# MCU063A_EtherCAT.net
KiCad netlist of a schematic drawn in Altium Designer
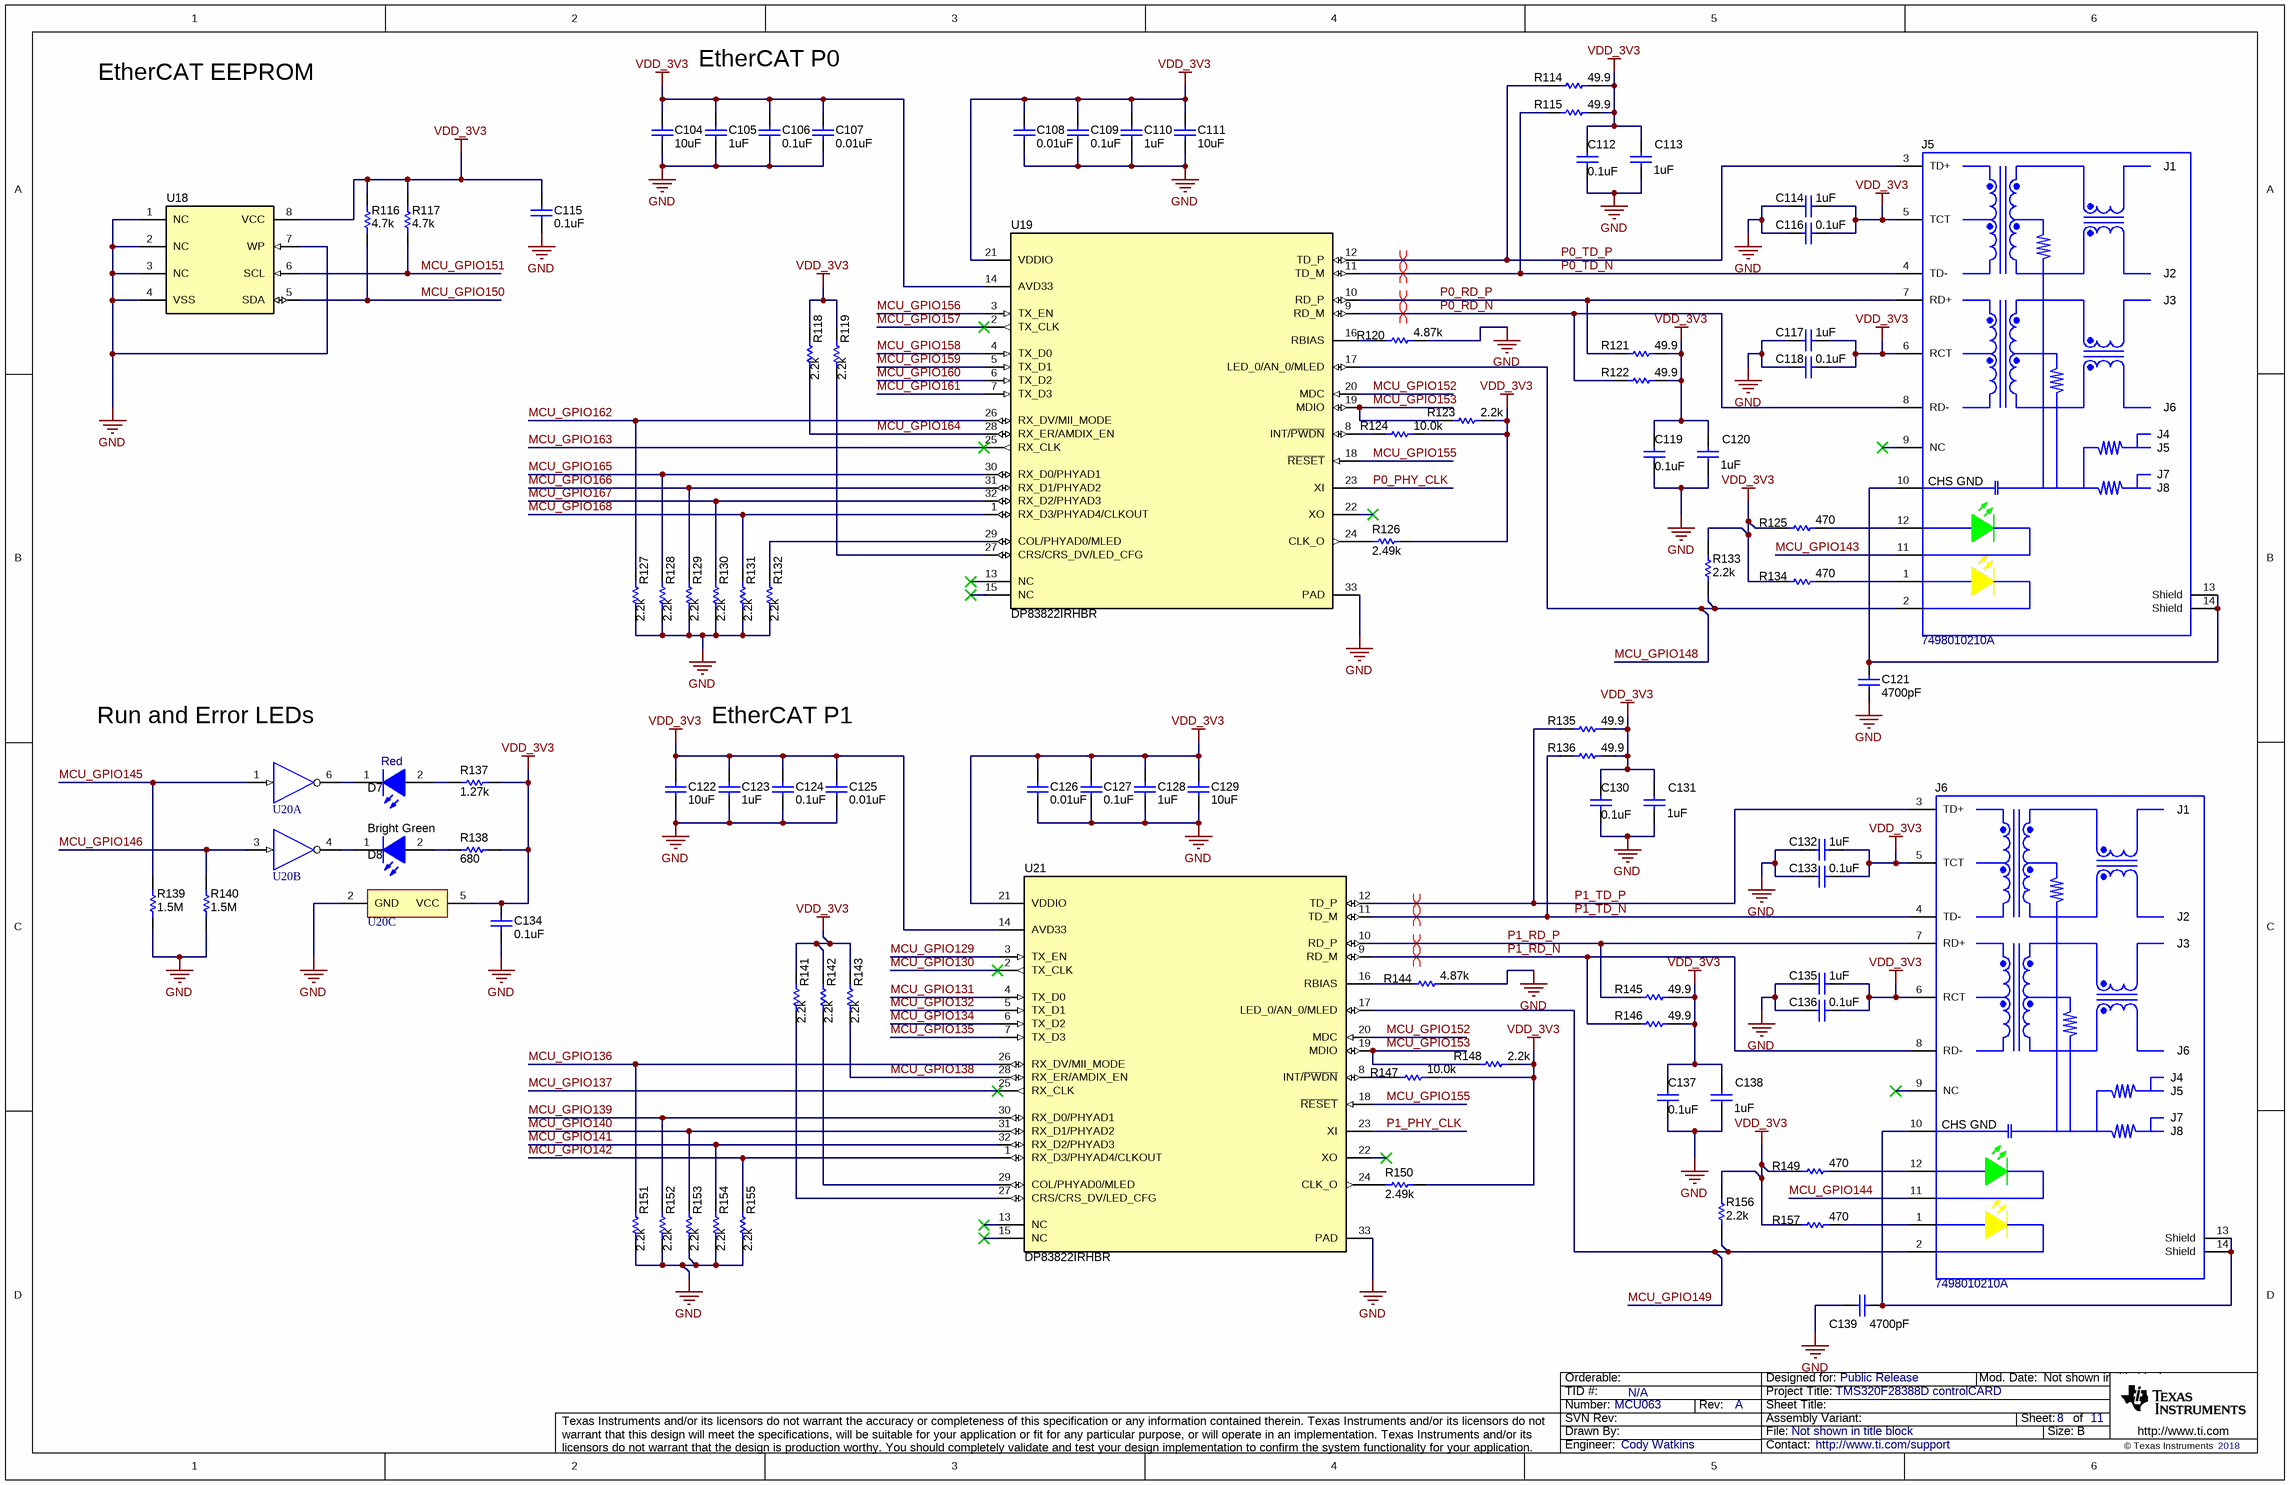
[diagram p0: MCU063A_EtherCAT.SchDoc]

(export (version "E")
  (design (tool "Eeschema 10.0.6"))
  (components
    (comp (ref "C104")
      (value "CL05A106MQ5NUNC")
      (footprint "0402")
      (description "CAP, CERM, 10 uF, 6.3 V, +/- 20%, X5R, 0402")
      (fields
        (field (name "MANUFACTURER") "Samsung Electro-Mechanics")
        (field (name "VALUEDISPLAYED") "10uF")
      )
      (libsource (lib "Altium Vault - TI") (part "Capacitor"))
    )
    (comp (ref "C105")
      (value "EMK105BJ105KVHF")
      (footprint "0402")
      (description "CAP, CERM, 1 uF, 16 V, +/- 10%, X5R, 0402")
      (fields (field (name "MANUFACTURER") "Taiyo Yuden") (field (name "VALUEDISPLAYED") "1uF"))
      (libsource (lib "Altium Vault - TI") (part "Capacitor"))
    )
    (comp (ref "C106")
      (value "LMK105BJ104KV-F")
      (footprint "0402")
      (description "CAP, CERM, 0.1 uF, 10 V,+/- 10%, X5R, 0402")
      (fields (field (name "MANUFACTURER") "Taiyo Yuden") (field (name "VALUEDISPLAYED") "0.1uF"))
      (libsource (lib "Altium Vault - TI") (part "Capacitor"))
    )
    (comp (ref "C107")
      (value "885012205031")
      (footprint "0402")
      (description "CAP, CERM, 0.01 uF, 16 V, +/- 10%, X7R, 0402")
      (fields (field (name "MANUFACTURER") "Wurth Elektronik") (field (name "VALUEDISPLAYED") "0.01uF"))
      (libsource (lib "Altium Vault - TI") (part "Capacitor"))
    )
    (comp (ref "C108")
      (value "885012205031")
      (footprint "0402")
      (description "CAP, CERM, 0.01 uF, 16 V, +/- 10%, X7R, 0402")
      (fields (field (name "MANUFACTURER") "Wurth Elektronik") (field (name "VALUEDISPLAYED") "0.01uF"))
      (libsource (lib "Altium Vault - TI") (part "Capacitor"))
    )
    (comp (ref "C109")
      (value "LMK105BJ104KV-F")
      (footprint "0402")
      (description "CAP, CERM, 0.1 uF, 10 V,+/- 10%, X5R, 0402")
      (fields (field (name "MANUFACTURER") "Taiyo Yuden") (field (name "VALUEDISPLAYED") "0.1uF"))
      (libsource (lib "Altium Vault - TI") (part "Capacitor"))
    )
    (comp (ref "C110")
      (value "EMK105BJ105KVHF")
      (footprint "0402")
      (description "CAP, CERM, 1 uF, 16 V, +/- 10%, X5R, 0402")
      (fields (field (name "MANUFACTURER") "Taiyo Yuden") (field (name "VALUEDISPLAYED") "1uF"))
      (libsource (lib "Altium Vault - TI") (part "Capacitor"))
    )
    (comp (ref "C111")
      (value "CL05A106MQ5NUNC")
      (footprint "0402")
      (description "CAP, CERM, 10 uF, 6.3 V, +/- 20%, X5R, 0402")
      (fields
        (field (name "MANUFACTURER") "Samsung Electro-Mechanics")
        (field (name "VALUEDISPLAYED") "10uF")
      )
      (libsource (lib "Altium Vault - TI") (part "Capacitor"))
    )
    (comp (ref "C112")
      (value "LMK105BJ104KV-F")
      (footprint "0402")
      (description "CAP, CERM, 0.1 uF, 10 V,+/- 10%, X5R, 0402")
      (fields (field (name "MANUFACTURER") "Taiyo Yuden") (field (name "VALUEDISPLAYED") "0.1uF"))
      (libsource (lib "Altium Vault - TI") (part "Capacitor"))
    )
    (comp (ref "C113")
      (value "EMK105BJ105KVHF")
      (footprint "0402")
      (description "CAP, CERM, 1 uF, 16 V, +/- 10%, X5R, 0402")
      (fields (field (name "MANUFACTURER") "Taiyo Yuden") (field (name "VALUEDISPLAYED") "1uF"))
      (libsource (lib "Altium Vault - TI") (part "Capacitor"))
    )
    (comp (ref "C114")
      (value "EMK105BJ105KVHF")
      (footprint "0402")
      (description "CAP, CERM, 1 uF, 16 V, +/- 10%, X5R, 0402")
      (fields (field (name "MANUFACTURER") "Taiyo Yuden") (field (name "VALUEDISPLAYED") "1uF"))
      (libsource (lib "Altium Vault - TI") (part "Capacitor"))
    )
    (comp (ref "C115")
      (value "CL05B104KP5NNNC")
      (footprint "0402")
      (description "CAP, CERM, 0.1 uF, 10 V, +/- 10%, X7R, 0402")
      (fields
        (field (name "VALUEDISPLAYED") "0.1uF")
        (field (name "MANUFACTURER") "Samsung Electro-Mechanics")
      )
      (libsource (lib "Altium Vault - TI") (part "Capacitor"))
    )
    (comp (ref "C116")
      (value "LMK105BJ104KV-F")
      (footprint "0402")
      (description "CAP, CERM, 0.1 uF, 10 V,+/- 10%, X5R, 0402")
      (fields (field (name "MANUFACTURER") "Taiyo Yuden") (field (name "VALUEDISPLAYED") "0.1uF"))
      (libsource (lib "Altium Vault - TI") (part "Capacitor"))
    )
    (comp (ref "C117")
      (value "EMK105BJ105KVHF")
      (footprint "0402")
      (description "CAP, CERM, 1 uF, 16 V, +/- 10%, X5R, 0402")
      (fields (field (name "MANUFACTURER") "Taiyo Yuden") (field (name "VALUEDISPLAYED") "1uF"))
      (libsource (lib "Altium Vault - TI") (part "Capacitor"))
    )
    (comp (ref "C118")
      (value "LMK105BJ104KV-F")
      (footprint "0402")
      (description "CAP, CERM, 0.1 uF, 10 V,+/- 10%, X5R, 0402")
      (fields (field (name "MANUFACTURER") "Taiyo Yuden") (field (name "VALUEDISPLAYED") "0.1uF"))
      (libsource (lib "Altium Vault - TI") (part "Capacitor"))
    )
    (comp (ref "C119")
      (value "LMK105BJ104KV-F")
      (footprint "0402")
      (description "CAP, CERM, 0.1 uF, 10 V,+/- 10%, X5R, 0402")
      (fields (field (name "MANUFACTURER") "Taiyo Yuden") (field (name "VALUEDISPLAYED") "0.1uF"))
      (libsource (lib "Altium Vault - TI") (part "Capacitor"))
    )
    (comp (ref "C120")
      (value "EMK105BJ105KVHF")
      (footprint "0402")
      (description "CAP, CERM, 1 uF, 16 V, +/- 10%, X5R, 0402")
      (fields (field (name "MANUFACTURER") "Taiyo Yuden") (field (name "VALUEDISPLAYED") "1uF"))
      (libsource (lib "Altium Vault - TI") (part "Capacitor"))
    )
    (comp (ref "C121")
      (value "12061C472KAT2A")
      (footprint "1206")
      (description "CAP, CERM, 4700 pF, 100 V, +/- 10%, X7R, 1206")
      (fields (field (name "MANUFACTURER") "AVX") (field (name "VALUEDISPLAYED") "4700pF"))
      (libsource (lib "Altium Vault - TI") (part "Capacitor"))
    )
    (comp (ref "C122")
      (value "CL05A106MQ5NUNC")
      (footprint "0402")
      (description "CAP, CERM, 10 uF, 6.3 V, +/- 20%, X5R, 0402")
      (fields
        (field (name "MANUFACTURER") "Samsung Electro-Mechanics")
        (field (name "VALUEDISPLAYED") "10uF")
      )
      (libsource (lib "Altium Vault - TI") (part "Capacitor"))
    )
    (comp (ref "C123")
      (value "EMK105BJ105KVHF")
      (footprint "0402")
      (description "CAP, CERM, 1 uF, 16 V, +/- 10%, X5R, 0402")
      (fields (field (name "MANUFACTURER") "Taiyo Yuden") (field (name "VALUEDISPLAYED") "1uF"))
      (libsource (lib "Altium Vault - TI") (part "Capacitor"))
    )
    (comp (ref "C124")
      (value "LMK105BJ104KV-F")
      (footprint "0402")
      (description "CAP, CERM, 0.1 uF, 10 V,+/- 10%, X5R, 0402")
      (fields (field (name "MANUFACTURER") "Taiyo Yuden") (field (name "VALUEDISPLAYED") "0.1uF"))
      (libsource (lib "Altium Vault - TI") (part "Capacitor"))
    )
    (comp (ref "C125")
      (value "885012205031")
      (footprint "0402")
      (description "CAP, CERM, 0.01 uF, 16 V, +/- 10%, X7R, 0402")
      (fields (field (name "MANUFACTURER") "Wurth Elektronik") (field (name "VALUEDISPLAYED") "0.01uF"))
      (libsource (lib "Altium Vault - TI") (part "Capacitor"))
    )
    (comp (ref "C126")
      (value "885012205031")
      (footprint "0402")
      (description "CAP, CERM, 0.01 uF, 16 V, +/- 10%, X7R, 0402")
      (fields (field (name "MANUFACTURER") "Wurth Elektronik") (field (name "VALUEDISPLAYED") "0.01uF"))
      (libsource (lib "Altium Vault - TI") (part "Capacitor"))
    )
    (comp (ref "C127")
      (value "LMK105BJ104KV-F")
      (footprint "0402")
      (description "CAP, CERM, 0.1 uF, 10 V,+/- 10%, X5R, 0402")
      (fields (field (name "MANUFACTURER") "Taiyo Yuden") (field (name "VALUEDISPLAYED") "0.1uF"))
      (libsource (lib "Altium Vault - TI") (part "Capacitor"))
    )
    (comp (ref "C128")
      (value "EMK105BJ105KVHF")
      (footprint "0402")
      (description "CAP, CERM, 1 uF, 16 V, +/- 10%, X5R, 0402")
      (fields (field (name "MANUFACTURER") "Taiyo Yuden") (field (name "VALUEDISPLAYED") "1uF"))
      (libsource (lib "Altium Vault - TI") (part "Capacitor"))
    )
    (comp (ref "C129")
      (value "CL05A106MQ5NUNC")
      (footprint "0402")
      (description "CAP, CERM, 10 uF, 6.3 V, +/- 20%, X5R, 0402")
      (fields
        (field (name "MANUFACTURER") "Samsung Electro-Mechanics")
        (field (name "VALUEDISPLAYED") "10uF")
      )
      (libsource (lib "Altium Vault - TI") (part "Capacitor"))
    )
    (comp (ref "C130")
      (value "LMK105BJ104KV-F")
      (footprint "0402")
      (description "CAP, CERM, 0.1 uF, 10 V,+/- 10%, X5R, 0402")
      (fields (field (name "MANUFACTURER") "Taiyo Yuden") (field (name "VALUEDISPLAYED") "0.1uF"))
      (libsource (lib "Altium Vault - TI") (part "Capacitor"))
    )
    (comp (ref "C131")
      (value "EMK105BJ105KVHF")
      (footprint "0402")
      (description "CAP, CERM, 1 uF, 16 V, +/- 10%, X5R, 0402")
      (fields (field (name "MANUFACTURER") "Taiyo Yuden") (field (name "VALUEDISPLAYED") "1uF"))
      (libsource (lib "Altium Vault - TI") (part "Capacitor"))
    )
    (comp (ref "C132")
      (value "EMK105BJ105KVHF")
      (footprint "0402")
      (description "CAP, CERM, 1 uF, 16 V, +/- 10%, X5R, 0402")
      (fields (field (name "MANUFACTURER") "Taiyo Yuden") (field (name "VALUEDISPLAYED") "1uF"))
      (libsource (lib "Altium Vault - TI") (part "Capacitor"))
    )
    (comp (ref "C133")
      (value "LMK105BJ104KV-F")
      (footprint "0402")
      (description "CAP, CERM, 0.1 uF, 10 V,+/- 10%, X5R, 0402")
      (fields (field (name "MANUFACTURER") "Taiyo Yuden") (field (name "VALUEDISPLAYED") "0.1uF"))
      (libsource (lib "Altium Vault - TI") (part "Capacitor"))
    )
    (comp (ref "C134")
      (value "CL05B104KP5NNNC")
      (footprint "0402")
      (description "CAP, CERM, 0.1 uF, 10 V, +/- 10%, X7R, 0402")
      (fields
        (field (name "VALUEDISPLAYED") "0.1uF")
        (field (name "MANUFACTURER") "Samsung Electro-Mechanics")
      )
      (libsource (lib "Altium Vault - TI") (part "Capacitor"))
    )
    (comp (ref "C135")
      (value "EMK105BJ105KVHF")
      (footprint "0402")
      (description "CAP, CERM, 1 uF, 16 V, +/- 10%, X5R, 0402")
      (fields (field (name "MANUFACTURER") "Taiyo Yuden") (field (name "VALUEDISPLAYED") "1uF"))
      (libsource (lib "Altium Vault - TI") (part "Capacitor"))
    )
    (comp (ref "C136")
      (value "LMK105BJ104KV-F")
      (footprint "0402")
      (description "CAP, CERM, 0.1 uF, 10 V,+/- 10%, X5R, 0402")
      (fields (field (name "MANUFACTURER") "Taiyo Yuden") (field (name "VALUEDISPLAYED") "0.1uF"))
      (libsource (lib "Altium Vault - TI") (part "Capacitor"))
    )
    (comp (ref "C137")
      (value "LMK105BJ104KV-F")
      (footprint "0402")
      (description "CAP, CERM, 0.1 uF, 10 V,+/- 10%, X5R, 0402")
      (fields (field (name "MANUFACTURER") "Taiyo Yuden") (field (name "VALUEDISPLAYED") "0.1uF"))
      (libsource (lib "Altium Vault - TI") (part "Capacitor"))
    )
    (comp (ref "C138")
      (value "EMK105BJ105KVHF")
      (footprint "0402")
      (description "CAP, CERM, 1 uF, 16 V, +/- 10%, X5R, 0402")
      (fields (field (name "MANUFACTURER") "Taiyo Yuden") (field (name "VALUEDISPLAYED") "1uF"))
      (libsource (lib "Altium Vault - TI") (part "Capacitor"))
    )
    (comp (ref "C139")
      (value "12061C472KAT2A")
      (footprint "1206")
      (description "CAP, CERM, 4700 pF, 100 V, +/- 10%, X7R, 1206")
      (fields (field (name "MANUFACTURER") "AVX") (field (name "VALUEDISPLAYED") "4700pF"))
      (libsource (lib "Altium Vault - TI") (part "Capacitor"))
    )
    (comp (ref "D7")
      (value "Red")
      (footprint "WL-SMCW_RED_0805")
      (description "LED, Red, SMD")
      (fields (field (name "PARTNUMBER") "150080SS75000") (field (name "MANUFACTURER") "Wurth Elektronik"))
      (libsource (lib "Altium Vault - TI") (part "LED_A2_K1"))
    )
    (comp (ref "D8")
      (value "Bright Green")
      (footprint "WL-SMCW_Green_0805")
      (description "LED, Bright Green, SMD")
      (fields (field (name "PARTNUMBER") "150080VS75000") (field (name "MANUFACTURER") "Wurth Elektronik"))
      (libsource (lib "Altium Vault - TI") (part "LED_A2_K1"))
    )
    (comp (ref "J5")
      (value "7498010210A")
      (footprint "Wurth_7498010210A")
      (description "Connector, RJ45, 1x1, Gold, R/A, SMT")
      (fields (field (name "MANUFACTURER") "Wurth Elektronik"))
      (libsource (lib "Altium Vault - TI") (part "Wurth_7498010210A"))
    )
    (comp (ref "J6")
      (value "7498010210A")
      (footprint "Wurth_7498010210A")
      (description "Connector, RJ45, 1x1, Gold, R/A, SMT")
      (fields (field (name "MANUFACTURER") "Wurth Elektronik"))
      (libsource (lib "Altium Vault - TI") (part "Wurth_7498010210A"))
    )
    (comp (ref "R114")
      (value "RC0402FR-0749R9L")
      (footprint "0402")
      (description "RES, 49.9, 1%, 0.063 W, 0402")
      (fields (field (name "MANUFACTURER") "Yageo America") (field (name "VALUEDISPLAYED") "49.9"))
      (libsource (lib "Altium Vault - TI") (part "Resistor"))
    )
    (comp (ref "R115")
      (value "RC0402FR-0749R9L")
      (footprint "0402")
      (description "RES, 49.9, 1%, 0.063 W, 0402")
      (fields (field (name "MANUFACTURER") "Yageo America") (field (name "VALUEDISPLAYED") "49.9"))
      (libsource (lib "Altium Vault - TI") (part "Resistor"))
    )
    (comp (ref "R116")
      (value "CRCW04024K70JNED")
      (footprint "0402")
      (description "RES, 4.7 k, 5%, 0.063 W, AEC-Q200 Grade 0, 0402")
      (fields (field (name "MANUFACTURER") "Vishay-Dale") (field (name "VALUEDISPLAYED") "4.7k"))
      (libsource (lib "Altium Vault - TI") (part "Resistor"))
    )
    (comp (ref "R117")
      (value "CRCW04024K70JNED")
      (footprint "0402")
      (description "RES, 4.7 k, 5%, 0.063 W, AEC-Q200 Grade 0, 0402")
      (fields (field (name "MANUFACTURER") "Vishay-Dale") (field (name "VALUEDISPLAYED") "4.7k"))
      (libsource (lib "Altium Vault - TI") (part "Resistor"))
    )
    (comp (ref "R118")
      (value "CRCW02012K20JNED")
      (footprint "0201")
      (description "RES, 2.2 k, 5%, 0.05 W, 0201")
      (fields (field (name "MANUFACTURER") "Vishay-Dale") (field (name "VALUEDISPLAYED") "2.2k"))
      (libsource (lib "Altium Vault - TI") (part "Resistor"))
    )
    (comp (ref "R119")
      (value "CRCW02012K20JNED")
      (footprint "0201")
      (description "RES, 2.2 k, 5%, 0.05 W, 0201")
      (fields (field (name "MANUFACTURER") "Vishay-Dale") (field (name "VALUEDISPLAYED") "2.2k"))
      (libsource (lib "Altium Vault - TI") (part "Resistor"))
    )
    (comp (ref "R120")
      (value "CRCW04024K87FKED")
      (footprint "0402")
      (description "RES, 4.87 k, 1%, 0.063 W, AEC-Q200 Grade 0, 0402")
      (fields (field (name "MANUFACTURER") "Vishay-Dale") (field (name "VALUEDISPLAYED") "4.87k"))
      (libsource (lib "Altium Vault - TI") (part "Resistor"))
    )
    (comp (ref "R121")
      (value "RC0402FR-0749R9L")
      (footprint "0402")
      (description "RES, 49.9, 1%, 0.063 W, 0402")
      (fields (field (name "MANUFACTURER") "Yageo America") (field (name "VALUEDISPLAYED") "49.9"))
      (libsource (lib "Altium Vault - TI") (part "Resistor"))
    )
    (comp (ref "R122")
      (value "RC0402FR-0749R9L")
      (footprint "0402")
      (description "RES, 49.9, 1%, 0.063 W, 0402")
      (fields (field (name "MANUFACTURER") "Yageo America") (field (name "VALUEDISPLAYED") "49.9"))
      (libsource (lib "Altium Vault - TI") (part "Resistor"))
    )
    (comp (ref "R123")
      (value "CRCW04022K20JNED")
      (footprint "0402")
      (description "RES, 2.2 k, 5%, 0.063 W, AEC-Q200 Grade 0, 0402")
      (fields (field (name "MANUFACTURER") "Vishay-Dale") (field (name "VALUEDISPLAYED") "2.2k"))
      (libsource (lib "Altium Vault - TI") (part "Resistor"))
    )
    (comp (ref "R124")
      (value "RC0402FR-0710KL")
      (footprint "0402")
      (description "RES, 10.0 k, 1%, 0.063 W, 0402")
      (fields (field (name "MANUFACTURER") "Yageo America") (field (name "VALUEDISPLAYED") "10.0k"))
      (libsource (lib "Altium Vault - TI") (part "Resistor"))
    )
    (comp (ref "R125")
      (value "CRCW0603470RJNEA")
      (footprint "0603")
      (description "RES, 470, 5%, 0.1 W, AEC-Q200 Grade 0, 0603")
      (fields (field (name "MANUFACTURER") "Vishay-Dale") (field (name "VALUEDISPLAYED") "470"))
      (libsource (lib "Altium Vault - TI") (part "Resistor"))
    )
    (comp (ref "R126")
      (value "CRCW04022K49FKED")
      (footprint "0402")
      (description "RES, 2.49 k, 1%, 0.063 W, AEC-Q200 Grade 0, 0402")
      (fields (field (name "MANUFACTURER") "Vishay-Dale") (field (name "VALUEDISPLAYED") "2.49k"))
      (libsource (lib "Altium Vault - TI") (part "Resistor"))
    )
    (comp (ref "R127")
      (value "CRCW02012K20JNED")
      (footprint "0201")
      (description "RES, 2.2 k, 5%, 0.05 W, 0201")
      (fields (field (name "MANUFACTURER") "Vishay-Dale") (field (name "VALUEDISPLAYED") "2.2k"))
      (libsource (lib "Altium Vault - TI") (part "Resistor"))
    )
    (comp (ref "R128")
      (value "CRCW02012K20JNED")
      (footprint "0201")
      (description "RES, 2.2 k, 5%, 0.05 W, 0201")
      (fields (field (name "MANUFACTURER") "Vishay-Dale") (field (name "VALUEDISPLAYED") "2.2k"))
      (libsource (lib "Altium Vault - TI") (part "Resistor"))
    )
    (comp (ref "R129")
      (value "CRCW02012K20JNED")
      (footprint "0201")
      (description "RES, 2.2 k, 5%, 0.05 W, 0201")
      (fields (field (name "MANUFACTURER") "Vishay-Dale") (field (name "VALUEDISPLAYED") "2.2k"))
      (libsource (lib "Altium Vault - TI") (part "Resistor"))
    )
    (comp (ref "R130")
      (value "CRCW02012K20JNED")
      (footprint "0201")
      (description "RES, 2.2 k, 5%, 0.05 W, 0201")
      (fields (field (name "MANUFACTURER") "Vishay-Dale") (field (name "VALUEDISPLAYED") "2.2k"))
      (libsource (lib "Altium Vault - TI") (part "Resistor"))
    )
    (comp (ref "R131")
      (value "CRCW02012K20JNED")
      (footprint "0201")
      (description "RES, 2.2 k, 5%, 0.05 W, 0201")
      (fields (field (name "MANUFACTURER") "Vishay-Dale") (field (name "VALUEDISPLAYED") "2.2k"))
      (libsource (lib "Altium Vault - TI") (part "Resistor"))
    )
    (comp (ref "R132")
      (value "CRCW02012K20JNED")
      (footprint "0201")
      (description "RES, 2.2 k, 5%, 0.05 W, 0201")
      (fields (field (name "MANUFACTURER") "Vishay-Dale") (field (name "VALUEDISPLAYED") "2.2k"))
      (libsource (lib "Altium Vault - TI") (part "Resistor"))
    )
    (comp (ref "R133")
      (value "CRCW04022K20JNED")
      (footprint "0402")
      (description "RES, 2.2 k, 5%, 0.063 W, AEC-Q200 Grade 0, 0402")
      (fields (field (name "MANUFACTURER") "Vishay-Dale") (field (name "VALUEDISPLAYED") "2.2k"))
      (libsource (lib "Altium Vault - TI") (part "Resistor"))
    )
    (comp (ref "R134")
      (value "CRCW0603470RJNEA")
      (footprint "0603")
      (description "RES, 470, 5%, 0.1 W, AEC-Q200 Grade 0, 0603")
      (fields (field (name "MANUFACTURER") "Vishay-Dale") (field (name "VALUEDISPLAYED") "470"))
      (libsource (lib "Altium Vault - TI") (part "Resistor"))
    )
    (comp (ref "R135")
      (value "RC0402FR-0749R9L")
      (footprint "0402")
      (description "RES, 49.9, 1%, 0.063 W, 0402")
      (fields (field (name "MANUFACTURER") "Yageo America") (field (name "VALUEDISPLAYED") "49.9"))
      (libsource (lib "Altium Vault - TI") (part "Resistor"))
    )
    (comp (ref "R136")
      (value "RC0402FR-0749R9L")
      (footprint "0402")
      (description "RES, 49.9, 1%, 0.063 W, 0402")
      (fields (field (name "MANUFACTURER") "Yageo America") (field (name "VALUEDISPLAYED") "49.9"))
      (libsource (lib "Altium Vault - TI") (part "Resistor"))
    )
    (comp (ref "R137")
      (value "CRCW04021K27FKED")
      (footprint "0402")
      (description "RES, 1.27 k, 1%, 0.063 W, AEC-Q200 Grade 0, 0402")
      (fields (field (name "MANUFACTURER") "Vishay-Dale") (field (name "VALUEDISPLAYED") "1.27k"))
      (libsource (lib "Altium Vault - TI") (part "Resistor"))
    )
    (comp (ref "R138")
      (value "CRCW0402680RJNED")
      (footprint "0402")
      (description "RES, 680, 5%, 0.063 W, AEC-Q200 Grade 0, 0402")
      (fields (field (name "VALUEDISPLAYED") "680") (field (name "MANUFACTURER") "Vishay-Dale"))
      (libsource (lib "Altium Vault - TI") (part "Resistor"))
    )
    (comp (ref "R139")
      (value "CRCW04021M50JNED")
      (footprint "0402")
      (description "RES, 1.5 M, 5%, 0.063 W, AEC-Q200 Grade 0, 0402")
      (fields (field (name "MANUFACTURER") "Vishay-Dale") (field (name "VALUEDISPLAYED") "1.5M"))
      (libsource (lib "Altium Vault - TI") (part "Resistor"))
    )
    (comp (ref "R140")
      (value "CRCW04021M50JNED")
      (footprint "0402")
      (description "RES, 1.5 M, 5%, 0.063 W, AEC-Q200 Grade 0, 0402")
      (fields (field (name "MANUFACTURER") "Vishay-Dale") (field (name "VALUEDISPLAYED") "1.5M"))
      (libsource (lib "Altium Vault - TI") (part "Resistor"))
    )
    (comp (ref "R141")
      (value "CRCW02012K20JNED")
      (footprint "0201")
      (description "RES, 2.2 k, 5%, 0.05 W, 0201")
      (fields (field (name "MANUFACTURER") "Vishay-Dale") (field (name "VALUEDISPLAYED") "2.2k"))
      (libsource (lib "Altium Vault - TI") (part "Resistor"))
    )
    (comp (ref "R142")
      (value "CRCW02012K20JNED")
      (footprint "0201")
      (description "RES, 2.2 k, 5%, 0.05 W, 0201")
      (fields (field (name "MANUFACTURER") "Vishay-Dale") (field (name "VALUEDISPLAYED") "2.2k"))
      (libsource (lib "Altium Vault - TI") (part "Resistor"))
    )
    (comp (ref "R143")
      (value "CRCW02012K20JNED")
      (footprint "0201")
      (description "RES, 2.2 k, 5%, 0.05 W, 0201")
      (fields (field (name "MANUFACTURER") "Vishay-Dale") (field (name "VALUEDISPLAYED") "2.2k"))
      (libsource (lib "Altium Vault - TI") (part "Resistor"))
    )
    (comp (ref "R144")
      (value "CRCW04024K87FKED")
      (footprint "0402")
      (description "RES, 4.87 k, 1%, 0.063 W, AEC-Q200 Grade 0, 0402")
      (fields (field (name "MANUFACTURER") "Vishay-Dale") (field (name "VALUEDISPLAYED") "4.87k"))
      (libsource (lib "Altium Vault - TI") (part "Resistor"))
    )
    (comp (ref "R145")
      (value "RC0402FR-0749R9L")
      (footprint "0402")
      (description "RES, 49.9, 1%, 0.063 W, 0402")
      (fields (field (name "MANUFACTURER") "Yageo America") (field (name "VALUEDISPLAYED") "49.9"))
      (libsource (lib "Altium Vault - TI") (part "Resistor"))
    )
    (comp (ref "R146")
      (value "RC0402FR-0749R9L")
      (footprint "0402")
      (description "RES, 49.9, 1%, 0.063 W, 0402")
      (fields (field (name "MANUFACTURER") "Yageo America") (field (name "VALUEDISPLAYED") "49.9"))
      (libsource (lib "Altium Vault - TI") (part "Resistor"))
    )
    (comp (ref "R147")
      (value "RC0402FR-0710KL")
      (footprint "0402")
      (description "RES, 10.0 k, 1%, 0.063 W, 0402")
      (fields (field (name "MANUFACTURER") "Yageo America") (field (name "VALUEDISPLAYED") "10.0k"))
      (libsource (lib "Altium Vault - TI") (part "Resistor"))
    )
    (comp (ref "R148")
      (value "CRCW04022K20JNED")
      (footprint "0402")
      (description "RES, 2.2 k, 5%, 0.063 W, AEC-Q200 Grade 0, 0402")
      (fields (field (name "MANUFACTURER") "Vishay-Dale") (field (name "VALUEDISPLAYED") "2.2k"))
      (libsource (lib "Altium Vault - TI") (part "Resistor"))
    )
    (comp (ref "R149")
      (value "CRCW0603470RJNEA")
      (footprint "0603")
      (description "RES, 470, 5%, 0.1 W, AEC-Q200 Grade 0, 0603")
      (fields (field (name "MANUFACTURER") "Vishay-Dale") (field (name "VALUEDISPLAYED") "470"))
      (libsource (lib "Altium Vault - TI") (part "Resistor"))
    )
    (comp (ref "R150")
      (value "CRCW04022K49FKED")
      (footprint "0402")
      (description "RES, 2.49 k, 1%, 0.063 W, AEC-Q200 Grade 0, 0402")
      (fields (field (name "MANUFACTURER") "Vishay-Dale") (field (name "VALUEDISPLAYED") "2.49k"))
      (libsource (lib "Altium Vault - TI") (part "Resistor"))
    )
    (comp (ref "R151")
      (value "CRCW02012K20JNED")
      (footprint "0201")
      (description "RES, 2.2 k, 5%, 0.05 W, 0201")
      (fields (field (name "MANUFACTURER") "Vishay-Dale") (field (name "VALUEDISPLAYED") "2.2k"))
      (libsource (lib "Altium Vault - TI") (part "Resistor"))
    )
    (comp (ref "R152")
      (value "CRCW02012K20JNED")
      (footprint "0201")
      (description "RES, 2.2 k, 5%, 0.05 W, 0201")
      (fields (field (name "MANUFACTURER") "Vishay-Dale") (field (name "VALUEDISPLAYED") "2.2k"))
      (libsource (lib "Altium Vault - TI") (part "Resistor"))
    )
    (comp (ref "R153")
      (value "CRCW02012K20JNED")
      (footprint "0201")
      (description "RES, 2.2 k, 5%, 0.05 W, 0201")
      (fields (field (name "MANUFACTURER") "Vishay-Dale") (field (name "VALUEDISPLAYED") "2.2k"))
      (libsource (lib "Altium Vault - TI") (part "Resistor"))
    )
    (comp (ref "R154")
      (value "CRCW02012K20JNED")
      (footprint "0201")
      (description "RES, 2.2 k, 5%, 0.05 W, 0201")
      (fields (field (name "MANUFACTURER") "Vishay-Dale") (field (name "VALUEDISPLAYED") "2.2k"))
      (libsource (lib "Altium Vault - TI") (part "Resistor"))
    )
    (comp (ref "R155")
      (value "CRCW02012K20JNED")
      (footprint "0201")
      (description "RES, 2.2 k, 5%, 0.05 W, 0201")
      (fields (field (name "MANUFACTURER") "Vishay-Dale") (field (name "VALUEDISPLAYED") "2.2k"))
      (libsource (lib "Altium Vault - TI") (part "Resistor"))
    )
    (comp (ref "R156")
      (value "CRCW04022K20JNED")
      (footprint "0402")
      (description "RES, 2.2 k, 5%, 0.063 W, AEC-Q200 Grade 0, 0402")
      (fields (field (name "MANUFACTURER") "Vishay-Dale") (field (name "VALUEDISPLAYED") "2.2k"))
      (libsource (lib "Altium Vault - TI") (part "Resistor"))
    )
    (comp (ref "R157")
      (value "CRCW0603470RJNEA")
      (footprint "0603")
      (description "RES, 470, 5%, 0.1 W, AEC-Q200 Grade 0, 0603")
      (fields (field (name "MANUFACTURER") "Vishay-Dale") (field (name "VALUEDISPLAYED") "470"))
      (libsource (lib "Altium Vault - TI") (part "Resistor"))
    )
    (comp (ref "U18")
      (value "CAT24C16WI-GT3")
      (footprint "SOIC-8")
      (description "16 Kb I2C EEPROM Serial, SOIC-8")
      (fields (field (name "MANUFACTURER") "ON Semiconductor"))
      (libsource (lib "Altium Vault - TI") (part "EEPROM_8P_1-3NC"))
    )
    (comp (ref "U19")
      (value "DP83822IRHBR")
      (footprint "RHB0032B")
      (description "Robust, Low Power 10/100 Ethernet Physical Layer Transceiver, RHB0032B (VQFN-32)")
      (fields
        (field (name "ALTERNATE PARTNUMBER") "DP83822IRHBT")
        (field (name "PARTNUMBER") "DP83822IRHBR")
        (field (name "MANUFACTURER") "Texas Instruments")
      )
      (libsource (lib "Altium Vault - TI") (part "DP83822"))
    )
    (comp (ref "U20")
      (value "SN74LVC2G06DBVR")
      (footprint "DBV0006A_N")
      (description "Dual Inverter Buffer/Driver with Open-Drain Output, DBV0006A, LARGE T&R")
      (fields
        (field (name "MANUFACTURER") "Texas Instruments")
        (field (name "GENERIC PART NUMBER") "SN74LVC2G06")
      )
      (libsource (lib "Altium Vault - TI") (part "TI-SN74XXX2G06-XX-6"))
    )
    (comp (ref "U21")
      (value "DP83822IRHBR")
      (footprint "RHB0032B")
      (description "Robust, Low Power 10/100 Ethernet Physical Layer Transceiver, RHB0032B (VQFN-32)")
      (fields
        (field (name "ALTERNATE PARTNUMBER") "DP83822IRHBT")
        (field (name "PARTNUMBER") "DP83822IRHBR")
        (field (name "MANUFACTURER") "Texas Instruments")
      )
      (libsource (lib "Altium Vault - TI") (part "DP83822"))
    )
  )
  (nets
    (net (code "1") (name "/MCU_GPIO129") (class "Default")
      (node (ref "U21") (pin "3") (pinfunction "TX_EN_3") (pintype "input"))
    )
    (net (code "2") (name "/MCU_GPIO130") (class "Default")
      (node (ref "U21") (pin "2") (pinfunction "TX_CLK_2") (pintype "output+no_connect"))
    )
    (net (code "3") (name "/MCU_GPIO131") (class "Default")
      (node (ref "U21") (pin "4") (pinfunction "TX_D0_4") (pintype "input"))
    )
    (net (code "4") (name "/MCU_GPIO132") (class "Default")
      (node (ref "U21") (pin "5") (pinfunction "TX_D1_5") (pintype "input"))
    )
    (net (code "5") (name "/MCU_GPIO134") (class "Default")
      (node (ref "U21") (pin "6") (pinfunction "TX_D2_6") (pintype "input"))
    )
    (net (code "6") (name "/MCU_GPIO135") (class "Default")
      (node (ref "U21") (pin "7") (pinfunction "TX_D3_7") (pintype "input"))
    )
    (net (code "7") (name "/MCU_GPIO136") (class "Default")
      (node (ref "R151") (pin "2") (pinfunction "2_2") (pintype "passive"))
      (node (ref "U21") (pin "26") (pinfunction "RX_DV/MII_MODE_26") (pintype "bidirectional"))
    )
    (net (code "8") (name "/MCU_GPIO137") (class "Default")
      (node (ref "U21") (pin "25") (pinfunction "RX_CLK_25") (pintype "output+no_connect"))
    )
    (net (code "9") (name "/MCU_GPIO138") (class "Default")
      (node (ref "R143") (pin "1") (pinfunction "1_1") (pintype "passive"))
      (node (ref "U21") (pin "28") (pinfunction "RX_ER/AMDIX_EN_28") (pintype "bidirectional"))
    )
    (net (code "10") (name "/MCU_GPIO139") (class "Default")
      (node (ref "R152") (pin "2") (pinfunction "2_2") (pintype "passive"))
      (node (ref "U21") (pin "30") (pinfunction "RX_D0/PHYAD1_30") (pintype "bidirectional"))
    )
    (net (code "11") (name "/MCU_GPIO140") (class "Default")
      (node (ref "R153") (pin "2") (pinfunction "2_2") (pintype "passive"))
      (node (ref "U21") (pin "31") (pinfunction "RX_D1/PHYAD2_31") (pintype "bidirectional"))
    )
    (net (code "12") (name "/MCU_GPIO141") (class "Default")
      (node (ref "R154") (pin "2") (pinfunction "2_2") (pintype "passive"))
      (node (ref "U21") (pin "32") (pinfunction "RX_D2/PHYAD3_32") (pintype "bidirectional"))
    )
    (net (code "13") (name "/MCU_GPIO142") (class "Default")
      (node (ref "R155") (pin "2") (pinfunction "2_2") (pintype "passive"))
      (node (ref "U21") (pin "1") (pinfunction "RX_D3/PHYAD4/CLKOUT_1") (pintype "bidirectional"))
    )
    (net (code "14") (name "/MCU_GPIO143") (class "Default")
      (node (ref "J5") (pin "11") (pinfunction "LEFT_LED_CATHODE_11") (pintype "passive"))
    )
    (net (code "15") (name "/MCU_GPIO144") (class "Default")
      (node (ref "J6") (pin "11") (pinfunction "LEFT_LED_CATHODE_11") (pintype "passive"))
    )
    (net (code "16") (name "/MCU_GPIO145") (class "Default")
      (node (ref "R139") (pin "1") (pinfunction "1_1") (pintype "passive"))
      (node (ref "U20") (pin "1") (pinfunction "1A_1") (pintype "input"))
    )
    (net (code "17") (name "/MCU_GPIO146") (class "Default")
      (node (ref "R140") (pin "1") (pinfunction "1_1") (pintype "passive"))
      (node (ref "U20") (pin "3") (pinfunction "2A_3") (pintype "input"))
    )
    (net (code "18") (name "/MCU_GPIO148") (class "Default")
      (node (ref "J5") (pin "2") (pinfunction "RIGHT_LED_CATHODE_2") (pintype "passive"))
      (node (ref "R133") (pin "1") (pinfunction "1_1") (pintype "passive"))
      (node (ref "U19") (pin "17") (pinfunction "LED_0/AN_0/MLED_17") (pintype "bidirectional"))
    )
    (net (code "19") (name "/MCU_GPIO149") (class "Default")
      (node (ref "J6") (pin "2") (pinfunction "RIGHT_LED_CATHODE_2") (pintype "passive"))
      (node (ref "R156") (pin "1") (pinfunction "1_1") (pintype "passive"))
      (node (ref "U21") (pin "17") (pinfunction "LED_0/AN_0/MLED_17") (pintype "bidirectional"))
    )
    (net (code "20") (name "/MCU_GPIO150") (class "Default")
      (node (ref "R116") (pin "1") (pinfunction "1_1") (pintype "passive"))
      (node (ref "U18") (pin "5") (pinfunction "SDA_5") (pintype "bidirectional"))
    )
    (net (code "21") (name "/MCU_GPIO151") (class "Default")
      (node (ref "R117") (pin "1") (pinfunction "1_1") (pintype "passive"))
      (node (ref "U18") (pin "6") (pinfunction "SCL_6") (pintype "input"))
    )
    (net (code "22") (name "/MCU_GPIO152") (class "Default")
      (node (ref "U19") (pin "20") (pinfunction "MDC_20") (pintype "input"))
      (node (ref "U21") (pin "20") (pinfunction "MDC_20") (pintype "input"))
    )
    (net (code "23") (name "/MCU_GPIO153") (class "Default")
      (node (ref "R123") (pin "2") (pinfunction "2_2") (pintype "passive"))
      (node (ref "R148") (pin "2") (pinfunction "2_2") (pintype "passive"))
      (node (ref "U19") (pin "19") (pinfunction "MDIO_19") (pintype "bidirectional"))
      (node (ref "U21") (pin "19") (pinfunction "MDIO_19") (pintype "bidirectional"))
    )
    (net (code "24") (name "/MCU_GPIO155") (class "Default")
      (node (ref "U19") (pin "18") (pinfunction "RESET_18") (pintype "input"))
      (node (ref "U21") (pin "18") (pinfunction "RESET_18") (pintype "input"))
    )
    (net (code "25") (name "/MCU_GPIO156") (class "Default")
      (node (ref "U19") (pin "3") (pinfunction "TX_EN_3") (pintype "input"))
    )
    (net (code "26") (name "/MCU_GPIO157") (class "Default")
      (node (ref "U19") (pin "2") (pinfunction "TX_CLK_2") (pintype "output+no_connect"))
    )
    (net (code "27") (name "/MCU_GPIO158") (class "Default")
      (node (ref "U19") (pin "4") (pinfunction "TX_D0_4") (pintype "input"))
    )
    (net (code "28") (name "/MCU_GPIO159") (class "Default")
      (node (ref "U19") (pin "5") (pinfunction "TX_D1_5") (pintype "input"))
    )
    (net (code "29") (name "/MCU_GPIO160") (class "Default")
      (node (ref "U19") (pin "6") (pinfunction "TX_D2_6") (pintype "input"))
    )
    (net (code "30") (name "/MCU_GPIO161") (class "Default")
      (node (ref "U19") (pin "7") (pinfunction "TX_D3_7") (pintype "input"))
    )
    (net (code "31") (name "/MCU_GPIO162") (class "Default")
      (node (ref "R127") (pin "2") (pinfunction "2_2") (pintype "passive"))
      (node (ref "U19") (pin "26") (pinfunction "RX_DV/MII_MODE_26") (pintype "bidirectional"))
    )
    (net (code "32") (name "/MCU_GPIO163") (class "Default")
      (node (ref "U19") (pin "25") (pinfunction "RX_CLK_25") (pintype "output+no_connect"))
    )
    (net (code "33") (name "/MCU_GPIO164") (class "Default")
      (node (ref "R118") (pin "1") (pinfunction "1_1") (pintype "passive"))
      (node (ref "U19") (pin "28") (pinfunction "RX_ER/AMDIX_EN_28") (pintype "bidirectional"))
    )
    (net (code "34") (name "/MCU_GPIO165") (class "Default")
      (node (ref "R128") (pin "2") (pinfunction "2_2") (pintype "passive"))
      (node (ref "U19") (pin "30") (pinfunction "RX_D0/PHYAD1_30") (pintype "bidirectional"))
    )
    (net (code "35") (name "/MCU_GPIO166") (class "Default")
      (node (ref "R129") (pin "2") (pinfunction "2_2") (pintype "passive"))
      (node (ref "U19") (pin "31") (pinfunction "RX_D1/PHYAD2_31") (pintype "bidirectional"))
    )
    (net (code "36") (name "/MCU_GPIO167") (class "Default")
      (node (ref "R130") (pin "2") (pinfunction "2_2") (pintype "passive"))
      (node (ref "U19") (pin "32") (pinfunction "RX_D2/PHYAD3_32") (pintype "bidirectional"))
    )
    (net (code "37") (name "/MCU_GPIO168") (class "Default")
      (node (ref "R131") (pin "2") (pinfunction "2_2") (pintype "passive"))
      (node (ref "U19") (pin "1") (pinfunction "RX_D3/PHYAD4/CLKOUT_1") (pintype "bidirectional"))
    )
    (net (code "38") (name "/P0_PHY_CLK") (class "Default")
      (node (ref "U19") (pin "23") (pinfunction "XI_23") (pintype "passive"))
    )
    (net (code "39") (name "/P0_RD_N") (class "Default")
      (node (ref "J5") (pin "8") (pinfunction "RD-_8") (pintype "passive"))
      (node (ref "R122") (pin "1") (pinfunction "1_1") (pintype "passive"))
      (node (ref "U19") (pin "9") (pinfunction "RD_M_9") (pintype "bidirectional"))
    )
    (net (code "40") (name "/P0_RD_P") (class "Default")
      (node (ref "J5") (pin "7") (pinfunction "RD+_7") (pintype "passive"))
      (node (ref "R121") (pin "1") (pinfunction "1_1") (pintype "passive"))
      (node (ref "U19") (pin "10") (pinfunction "RD_P_10") (pintype "bidirectional"))
    )
    (net (code "41") (name "/P0_TD_N") (class "Default")
      (node (ref "J5") (pin "4") (pinfunction "TD-_4") (pintype "passive"))
      (node (ref "R115") (pin "1") (pinfunction "1_1") (pintype "passive"))
      (node (ref "U19") (pin "11") (pinfunction "TD_M_11") (pintype "bidirectional"))
    )
    (net (code "42") (name "/P0_TD_P") (class "Default")
      (node (ref "J5") (pin "3") (pinfunction "TD+_3") (pintype "passive"))
      (node (ref "R114") (pin "1") (pinfunction "1_1") (pintype "passive"))
      (node (ref "U19") (pin "12") (pinfunction "TD_P_12") (pintype "bidirectional"))
    )
    (net (code "43") (name "/P1_PHY_CLK") (class "Default")
      (node (ref "U21") (pin "23") (pinfunction "XI_23") (pintype "passive"))
    )
    (net (code "44") (name "/P1_RD_N") (class "Default")
      (node (ref "J6") (pin "8") (pinfunction "RD-_8") (pintype "passive"))
      (node (ref "R146") (pin "1") (pinfunction "1_1") (pintype "passive"))
      (node (ref "U21") (pin "9") (pinfunction "RD_M_9") (pintype "bidirectional"))
    )
    (net (code "45") (name "/P1_RD_P") (class "Default")
      (node (ref "J6") (pin "7") (pinfunction "RD+_7") (pintype "passive"))
      (node (ref "R145") (pin "1") (pinfunction "1_1") (pintype "passive"))
      (node (ref "U21") (pin "10") (pinfunction "RD_P_10") (pintype "bidirectional"))
    )
    (net (code "46") (name "/P1_TD_N") (class "Default")
      (node (ref "J6") (pin "4") (pinfunction "TD-_4") (pintype "passive"))
      (node (ref "R136") (pin "1") (pinfunction "1_1") (pintype "passive"))
      (node (ref "U21") (pin "11") (pinfunction "TD_M_11") (pintype "bidirectional"))
    )
    (net (code "47") (name "/P1_TD_P") (class "Default")
      (node (ref "J6") (pin "3") (pinfunction "TD+_3") (pintype "passive"))
      (node (ref "R135") (pin "1") (pinfunction "1_1") (pintype "passive"))
      (node (ref "U21") (pin "12") (pinfunction "TD_P_12") (pintype "bidirectional"))
    )
    (net (code "48") (name "GND") (class "Default")
      (node (ref "C104") (pin "2") (pinfunction "2_2") (pintype "passive"))
      (node (ref "C105") (pin "2") (pinfunction "2_2") (pintype "passive"))
      (node (ref "C106") (pin "2") (pinfunction "2_2") (pintype "passive"))
      (node (ref "C107") (pin "2") (pinfunction "2_2") (pintype "passive"))
      (node (ref "C108") (pin "2") (pinfunction "2_2") (pintype "passive"))
      (node (ref "C109") (pin "2") (pinfunction "2_2") (pintype "passive"))
      (node (ref "C110") (pin "2") (pinfunction "2_2") (pintype "passive"))
      (node (ref "C111") (pin "2") (pinfunction "2_2") (pintype "passive"))
      (node (ref "C112") (pin "2") (pinfunction "2_2") (pintype "passive"))
      (node (ref "C113") (pin "2") (pinfunction "2_2") (pintype "passive"))
      (node (ref "C114") (pin "1") (pinfunction "1_1") (pintype "passive"))
      (node (ref "C115") (pin "2") (pinfunction "2_2") (pintype "passive"))
      (node (ref "C116") (pin "1") (pinfunction "1_1") (pintype "passive"))
      (node (ref "C117") (pin "1") (pinfunction "1_1") (pintype "passive"))
      (node (ref "C118") (pin "1") (pinfunction "1_1") (pintype "passive"))
      (node (ref "C119") (pin "2") (pinfunction "2_2") (pintype "passive"))
      (node (ref "C120") (pin "2") (pinfunction "2_2") (pintype "passive"))
      (node (ref "C121") (pin "1") (pinfunction "1_1") (pintype "passive"))
      (node (ref "C122") (pin "2") (pinfunction "2_2") (pintype "passive"))
      (node (ref "C123") (pin "2") (pinfunction "2_2") (pintype "passive"))
      (node (ref "C124") (pin "2") (pinfunction "2_2") (pintype "passive"))
      (node (ref "C125") (pin "2") (pinfunction "2_2") (pintype "passive"))
      (node (ref "C126") (pin "2") (pinfunction "2_2") (pintype "passive"))
      (node (ref "C127") (pin "2") (pinfunction "2_2") (pintype "passive"))
      (node (ref "C128") (pin "2") (pinfunction "2_2") (pintype "passive"))
      (node (ref "C129") (pin "2") (pinfunction "2_2") (pintype "passive"))
      (node (ref "C130") (pin "2") (pinfunction "2_2") (pintype "passive"))
      (node (ref "C131") (pin "2") (pinfunction "2_2") (pintype "passive"))
      (node (ref "C132") (pin "1") (pinfunction "1_1") (pintype "passive"))
      (node (ref "C133") (pin "1") (pinfunction "1_1") (pintype "passive"))
      (node (ref "C134") (pin "2") (pinfunction "2_2") (pintype "passive"))
      (node (ref "C135") (pin "1") (pinfunction "1_1") (pintype "passive"))
      (node (ref "C136") (pin "1") (pinfunction "1_1") (pintype "passive"))
      (node (ref "C137") (pin "2") (pinfunction "2_2") (pintype "passive"))
      (node (ref "C138") (pin "2") (pinfunction "2_2") (pintype "passive"))
      (node (ref "C139") (pin "1") (pinfunction "1_1") (pintype "passive"))
      (node (ref "R120") (pin "2") (pinfunction "2_2") (pintype "passive"))
      (node (ref "R127") (pin "1") (pinfunction "1_1") (pintype "passive"))
      (node (ref "R128") (pin "1") (pinfunction "1_1") (pintype "passive"))
      (node (ref "R129") (pin "1") (pinfunction "1_1") (pintype "passive"))
      (node (ref "R130") (pin "1") (pinfunction "1_1") (pintype "passive"))
      (node (ref "R131") (pin "1") (pinfunction "1_1") (pintype "passive"))
      (node (ref "R132") (pin "1") (pinfunction "1_1") (pintype "passive"))
      (node (ref "R139") (pin "2") (pinfunction "2_2") (pintype "passive"))
      (node (ref "R140") (pin "2") (pinfunction "2_2") (pintype "passive"))
      (node (ref "R144") (pin "2") (pinfunction "2_2") (pintype "passive"))
      (node (ref "R151") (pin "1") (pinfunction "1_1") (pintype "passive"))
      (node (ref "R152") (pin "1") (pinfunction "1_1") (pintype "passive"))
      (node (ref "R153") (pin "1") (pinfunction "1_1") (pintype "passive"))
      (node (ref "R154") (pin "1") (pinfunction "1_1") (pintype "passive"))
      (node (ref "R155") (pin "1") (pinfunction "1_1") (pintype "passive"))
      (node (ref "U18") (pin "1") (pinfunction "NC_1") (pintype "passive"))
      (node (ref "U18") (pin "2") (pinfunction "NC_2") (pintype "passive"))
      (node (ref "U18") (pin "3") (pinfunction "NC_3") (pintype "passive"))
      (node (ref "U18") (pin "4") (pinfunction "VSS_4") (pintype "power_in"))
      (node (ref "U18") (pin "7") (pinfunction "WP_7") (pintype "input"))
      (node (ref "U19") (pin "33") (pinfunction "PAD_33") (pintype "power_in"))
      (node (ref "U20") (pin "2") (pinfunction "GND_2") (pintype "power_in"))
      (node (ref "U21") (pin "33") (pinfunction "PAD_33") (pintype "power_in"))
    )
    (net (code "49") (name "Net-(D7-A)") (class "Default")
      (node (ref "D7") (pin "2") (pinfunction "A_2") (pintype "passive"))
      (node (ref "R137") (pin "1") (pinfunction "1_1") (pintype "passive"))
    )
    (net (code "50") (name "Net-(D7-K)") (class "Default")
      (node (ref "D7") (pin "1") (pinfunction "K_1") (pintype "passive"))
      (node (ref "U20") (pin "6") (pinfunction "1Y_6") (pintype "open_collector"))
    )
    (net (code "51") (name "Net-(D8-A)") (class "Default")
      (node (ref "D8") (pin "2") (pinfunction "A_2") (pintype "passive"))
      (node (ref "R138") (pin "2") (pinfunction "2_2") (pintype "passive"))
    )
    (net (code "52") (name "Net-(D8-K)") (class "Default")
      (node (ref "D8") (pin "1") (pinfunction "K_1") (pintype "passive"))
      (node (ref "U20") (pin "4") (pinfunction "2Y_4") (pintype "open_collector"))
    )
    (net (code "53") (name "Net-(J5-CHS_GND)") (class "Default")
      (node (ref "C121") (pin "2") (pinfunction "2_2") (pintype "passive"))
      (node (ref "J5") (pin "10") (pinfunction "CHS_GND_10") (pintype "power_in"))
      (node (ref "J5") (pin "13") (pinfunction "Shield_13") (pintype "passive"))
      (node (ref "J5") (pin "14") (pinfunction "Shield_14") (pintype "passive"))
    )
    (net (code "54") (name "Net-(J5-LEFT_LED_ANODE)") (class "Default")
      (node (ref "J5") (pin "12") (pinfunction "LEFT_LED_ANODE_12") (pintype "passive"))
      (node (ref "R125") (pin "2") (pinfunction "2_2") (pintype "passive"))
    )
    (net (code "55") (name "Net-(J5-RIGHT_LED_ANODE)") (class "Default")
      (node (ref "J5") (pin "1") (pinfunction "RIGHT_LED_ANODE_1") (pintype "passive"))
      (node (ref "R134") (pin "2") (pinfunction "2_2") (pintype "passive"))
    )
    (net (code "56") (name "Net-(J6-CHS_GND)") (class "Default")
      (node (ref "C139") (pin "2") (pinfunction "2_2") (pintype "passive"))
      (node (ref "J6") (pin "10") (pinfunction "CHS_GND_10") (pintype "power_in"))
      (node (ref "J6") (pin "13") (pinfunction "Shield_13") (pintype "passive"))
      (node (ref "J6") (pin "14") (pinfunction "Shield_14") (pintype "passive"))
    )
    (net (code "57") (name "Net-(J6-LEFT_LED_ANODE)") (class "Default")
      (node (ref "J6") (pin "12") (pinfunction "LEFT_LED_ANODE_12") (pintype "passive"))
      (node (ref "R149") (pin "2") (pinfunction "2_2") (pintype "passive"))
    )
    (net (code "58") (name "Net-(J6-RIGHT_LED_ANODE)") (class "Default")
      (node (ref "J6") (pin "1") (pinfunction "RIGHT_LED_ANODE_1") (pintype "passive"))
      (node (ref "R157") (pin "2") (pinfunction "2_2") (pintype "passive"))
    )
    (net (code "59") (name "Net-(U19-CLK_O)") (class "Default")
      (node (ref "R126") (pin "2") (pinfunction "2_2") (pintype "passive"))
      (node (ref "U19") (pin "24") (pinfunction "CLK_O_24") (pintype "output"))
    )
    (net (code "60") (name "Net-(U19-COL{slash}PHYAD0{slash}MLED)") (class "Default")
      (node (ref "R132") (pin "2") (pinfunction "2_2") (pintype "passive"))
      (node (ref "U19") (pin "29") (pinfunction "COL/PHYAD0/MLED_29") (pintype "bidirectional"))
    )
    (net (code "61") (name "Net-(U19-CRS{slash}CRS_DV{slash}LED_CFG)") (class "Default")
      (node (ref "R119") (pin "1") (pinfunction "1_1") (pintype "passive"))
      (node (ref "U19") (pin "27") (pinfunction "CRS/CRS_DV/LED_CFG_27") (pintype "bidirectional"))
    )
    (net (code "62") (name "Net-(U19-INT{slash}~{PWDN})") (class "Default")
      (node (ref "R124") (pin "1") (pinfunction "1_1") (pintype "passive"))
      (node (ref "U19") (pin "8") (pinfunction "INT/~{PWDN}_8") (pintype "bidirectional"))
    )
    (net (code "63") (name "Net-(U19-RBIAS)") (class "Default")
      (node (ref "R120") (pin "1") (pinfunction "1_1") (pintype "passive"))
      (node (ref "U19") (pin "16") (pinfunction "RBIAS_16") (pintype "passive"))
    )
    (net (code "64") (name "Net-(U21-CLK_O)") (class "Default")
      (node (ref "R150") (pin "2") (pinfunction "2_2") (pintype "passive"))
      (node (ref "U21") (pin "24") (pinfunction "CLK_O_24") (pintype "output"))
    )
    (net (code "65") (name "Net-(U21-COL{slash}PHYAD0{slash}MLED)") (class "Default")
      (node (ref "R142") (pin "1") (pinfunction "1_1") (pintype "passive"))
      (node (ref "U21") (pin "29") (pinfunction "COL/PHYAD0/MLED_29") (pintype "bidirectional"))
    )
    (net (code "66") (name "Net-(U21-CRS{slash}CRS_DV{slash}LED_CFG)") (class "Default")
      (node (ref "R141") (pin "1") (pinfunction "1_1") (pintype "passive"))
      (node (ref "U21") (pin "27") (pinfunction "CRS/CRS_DV/LED_CFG_27") (pintype "bidirectional"))
    )
    (net (code "67") (name "Net-(U21-INT{slash}~{PWDN})") (class "Default")
      (node (ref "R147") (pin "1") (pinfunction "1_1") (pintype "passive"))
      (node (ref "U21") (pin "8") (pinfunction "INT/~{PWDN}_8") (pintype "bidirectional"))
    )
    (net (code "68") (name "Net-(U21-RBIAS)") (class "Default")
      (node (ref "R144") (pin "1") (pinfunction "1_1") (pintype "passive"))
      (node (ref "U21") (pin "16") (pinfunction "RBIAS_16") (pintype "passive"))
    )
    (net (code "69") (name "VDD_3V3") (class "Default")
      (node (ref "C104") (pin "1") (pinfunction "1_1") (pintype "passive"))
      (node (ref "C105") (pin "1") (pinfunction "1_1") (pintype "passive"))
      (node (ref "C106") (pin "1") (pinfunction "1_1") (pintype "passive"))
      (node (ref "C107") (pin "1") (pinfunction "1_1") (pintype "passive"))
      (node (ref "C108") (pin "1") (pinfunction "1_1") (pintype "passive"))
      (node (ref "C109") (pin "1") (pinfunction "1_1") (pintype "passive"))
      (node (ref "C110") (pin "1") (pinfunction "1_1") (pintype "passive"))
      (node (ref "C111") (pin "1") (pinfunction "1_1") (pintype "passive"))
      (node (ref "C112") (pin "1") (pinfunction "1_1") (pintype "passive"))
      (node (ref "C113") (pin "1") (pinfunction "1_1") (pintype "passive"))
      (node (ref "C114") (pin "2") (pinfunction "2_2") (pintype "passive"))
      (node (ref "C115") (pin "1") (pinfunction "1_1") (pintype "passive"))
      (node (ref "C116") (pin "2") (pinfunction "2_2") (pintype "passive"))
      (node (ref "C117") (pin "2") (pinfunction "2_2") (pintype "passive"))
      (node (ref "C118") (pin "2") (pinfunction "2_2") (pintype "passive"))
      (node (ref "C119") (pin "1") (pinfunction "1_1") (pintype "passive"))
      (node (ref "C120") (pin "1") (pinfunction "1_1") (pintype "passive"))
      (node (ref "C122") (pin "1") (pinfunction "1_1") (pintype "passive"))
      (node (ref "C123") (pin "1") (pinfunction "1_1") (pintype "passive"))
      (node (ref "C124") (pin "1") (pinfunction "1_1") (pintype "passive"))
      (node (ref "C125") (pin "1") (pinfunction "1_1") (pintype "passive"))
      (node (ref "C126") (pin "1") (pinfunction "1_1") (pintype "passive"))
      (node (ref "C127") (pin "1") (pinfunction "1_1") (pintype "passive"))
      (node (ref "C128") (pin "1") (pinfunction "1_1") (pintype "passive"))
      (node (ref "C129") (pin "1") (pinfunction "1_1") (pintype "passive"))
      (node (ref "C130") (pin "1") (pinfunction "1_1") (pintype "passive"))
      (node (ref "C131") (pin "1") (pinfunction "1_1") (pintype "passive"))
      (node (ref "C132") (pin "2") (pinfunction "2_2") (pintype "passive"))
      (node (ref "C133") (pin "2") (pinfunction "2_2") (pintype "passive"))
      (node (ref "C134") (pin "1") (pinfunction "1_1") (pintype "passive"))
      (node (ref "C135") (pin "2") (pinfunction "2_2") (pintype "passive"))
      (node (ref "C136") (pin "2") (pinfunction "2_2") (pintype "passive"))
      (node (ref "C137") (pin "1") (pinfunction "1_1") (pintype "passive"))
      (node (ref "C138") (pin "1") (pinfunction "1_1") (pintype "passive"))
      (node (ref "J5") (pin "5") (pinfunction "TCT_5") (pintype "passive"))
      (node (ref "J5") (pin "6") (pinfunction "RCT_6") (pintype "passive"))
      (node (ref "J6") (pin "5") (pinfunction "TCT_5") (pintype "passive"))
      (node (ref "J6") (pin "6") (pinfunction "RCT_6") (pintype "passive"))
      (node (ref "R114") (pin "2") (pinfunction "2_2") (pintype "passive"))
      (node (ref "R115") (pin "2") (pinfunction "2_2") (pintype "passive"))
      (node (ref "R116") (pin "2") (pinfunction "2_2") (pintype "passive"))
      (node (ref "R117") (pin "2") (pinfunction "2_2") (pintype "passive"))
      (node (ref "R118") (pin "2") (pinfunction "2_2") (pintype "passive"))
      (node (ref "R119") (pin "2") (pinfunction "2_2") (pintype "passive"))
      (node (ref "R121") (pin "2") (pinfunction "2_2") (pintype "passive"))
      (node (ref "R122") (pin "2") (pinfunction "2_2") (pintype "passive"))
      (node (ref "R123") (pin "1") (pinfunction "1_1") (pintype "passive"))
      (node (ref "R124") (pin "2") (pinfunction "2_2") (pintype "passive"))
      (node (ref "R125") (pin "1") (pinfunction "1_1") (pintype "passive"))
      (node (ref "R126") (pin "1") (pinfunction "1_1") (pintype "passive"))
      (node (ref "R133") (pin "2") (pinfunction "2_2") (pintype "passive"))
      (node (ref "R134") (pin "1") (pinfunction "1_1") (pintype "passive"))
      (node (ref "R135") (pin "2") (pinfunction "2_2") (pintype "passive"))
      (node (ref "R136") (pin "2") (pinfunction "2_2") (pintype "passive"))
      (node (ref "R137") (pin "2") (pinfunction "2_2") (pintype "passive"))
      (node (ref "R138") (pin "1") (pinfunction "1_1") (pintype "passive"))
      (node (ref "R141") (pin "2") (pinfunction "2_2") (pintype "passive"))
      (node (ref "R142") (pin "2") (pinfunction "2_2") (pintype "passive"))
      (node (ref "R143") (pin "2") (pinfunction "2_2") (pintype "passive"))
      (node (ref "R145") (pin "2") (pinfunction "2_2") (pintype "passive"))
      (node (ref "R146") (pin "2") (pinfunction "2_2") (pintype "passive"))
      (node (ref "R147") (pin "2") (pinfunction "2_2") (pintype "passive"))
      (node (ref "R148") (pin "1") (pinfunction "1_1") (pintype "passive"))
      (node (ref "R149") (pin "1") (pinfunction "1_1") (pintype "passive"))
      (node (ref "R150") (pin "1") (pinfunction "1_1") (pintype "passive"))
      (node (ref "R156") (pin "2") (pinfunction "2_2") (pintype "passive"))
      (node (ref "R157") (pin "1") (pinfunction "1_1") (pintype "passive"))
      (node (ref "U18") (pin "8") (pinfunction "VCC_8") (pintype "power_in"))
      (node (ref "U19") (pin "14") (pinfunction "AVD33_14") (pintype "power_in"))
      (node (ref "U19") (pin "21") (pinfunction "VDDIO_21") (pintype "power_in"))
      (node (ref "U20") (pin "5") (pinfunction "VCC_5") (pintype "power_in"))
      (node (ref "U21") (pin "14") (pinfunction "AVD33_14") (pintype "power_in"))
      (node (ref "U21") (pin "21") (pinfunction "VDDIO_21") (pintype "power_in"))
    )
    (net (code "70") (name "unconnected-(J5-NC-Pad9)") (class "Default")
      (node (ref "J5") (pin "9") (pinfunction "NC_9") (pintype "passive+no_connect"))
    )
    (net (code "71") (name "unconnected-(J6-NC-Pad9)") (class "Default")
      (node (ref "J6") (pin "9") (pinfunction "NC_9") (pintype "passive+no_connect"))
    )
    (net (code "72") (name "unconnected-(U19-NC-Pad13)") (class "Default")
      (node (ref "U19") (pin "13") (pinfunction "NC_13") (pintype "passive+no_connect"))
    )
    (net (code "73") (name "unconnected-(U19-NC-Pad15)") (class "Default")
      (node (ref "U19") (pin "15") (pinfunction "NC_15") (pintype "passive+no_connect"))
    )
    (net (code "74") (name "unconnected-(U19-XO-Pad22)") (class "Default")
      (node (ref "U19") (pin "22") (pinfunction "XO_22") (pintype "passive+no_connect"))
    )
    (net (code "75") (name "unconnected-(U21-NC-Pad13)") (class "Default")
      (node (ref "U21") (pin "13") (pinfunction "NC_13") (pintype "passive+no_connect"))
    )
    (net (code "76") (name "unconnected-(U21-NC-Pad15)") (class "Default")
      (node (ref "U21") (pin "15") (pinfunction "NC_15") (pintype "passive+no_connect"))
    )
    (net (code "77") (name "unconnected-(U21-XO-Pad22)") (class "Default")
      (node (ref "U21") (pin "22") (pinfunction "XO_22") (pintype "passive+no_connect"))
    )
  )
)
